# PCB_ArduinoShield_v2.net
KiCad netlist of a schematic drawn in EasyEDA
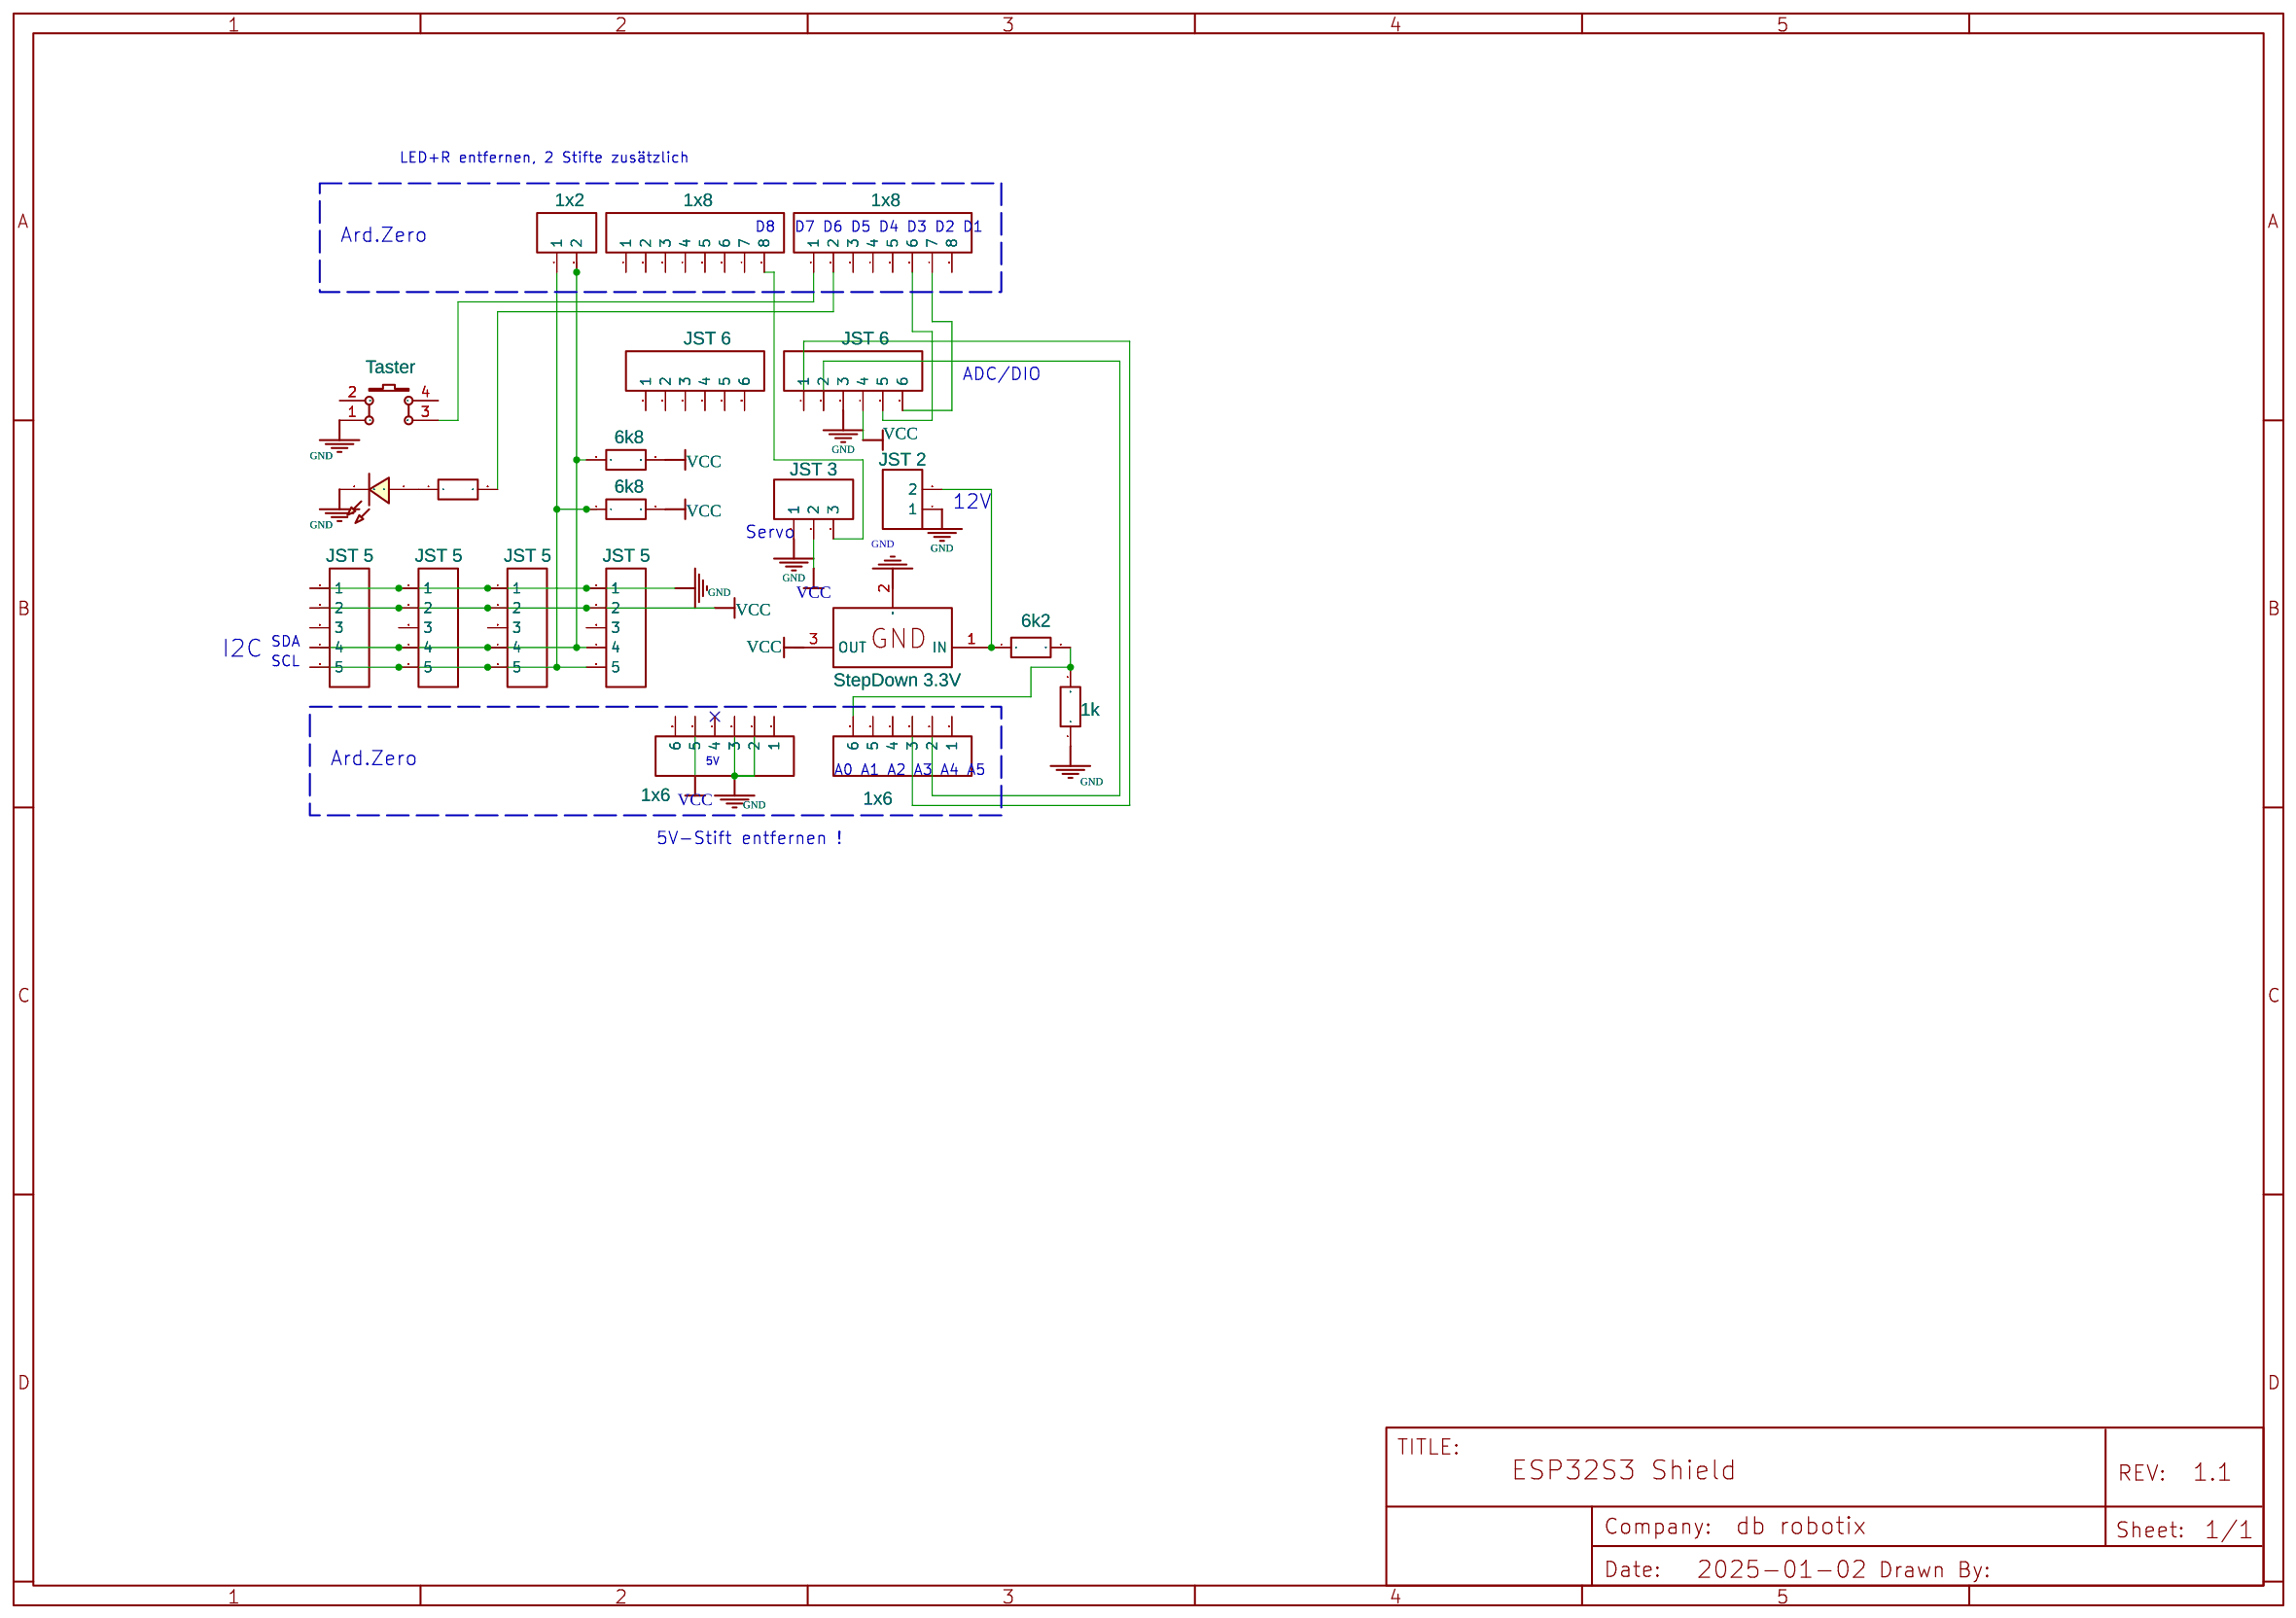
[diagram p0: schematic sheet]

(export (version "E")
  (design (tool "Eeschema 10.0.6"))
  (components
    (comp (ref "H1") (value "1x8") (libsource (lib "") (part "HDR-F-2.54_1x8")))
    (comp (ref "H2") (value "1x8") (libsource (lib "") (part "HDR-F-2.54_1x8")))
    (comp (ref "H3") (value "1x2") (libsource (lib "") (part "HDR-F-2.54_1x2")))
    (comp (ref "H4") (value "1x6") (libsource (lib "") (part "HDR-F-2.54_1x6_1")))
    (comp (ref "H5") (value "1x6") (libsource (lib "") (part "HDR-F-2.54_1x6_1")))
    (comp (ref "H6") (value "JST 6") (libsource (lib "") (part "HDR-F-2.54_1x6")))
    (comp (ref "H7") (value "JST 6") (libsource (lib "") (part "HDR-F-2.54_1x6")))
    (comp (ref "H8") (value "JST 3") (libsource (lib "") (part "HDR-F-2.54_1x3")))
    (comp (ref "H9") (value "JST 5") (libsource (lib "") (part "HDR-F-2.54_1x5")))
    (comp (ref "H10") (value "JST 5") (libsource (lib "") (part "HDR-F-2.54_1x5")))
    (comp (ref "H11") (value "JST 5") (libsource (lib "") (part "HDR-F-2.54_1x5")))
    (comp (ref "H12") (value "JST 5") (libsource (lib "") (part "HDR-F-2.54_1x5")))
    (comp (ref "H13") (value "JST 2") (libsource (lib "") (part "HDR-F-2.54_1x2_1")))
    (comp (ref "KEY1")
      (value "Taster")
      (fields (field (name "Manufacturer Part") "K2-1102DP-E4SW-04") (field (name "Manufacturer") "韩国韩荣"))
      (libsource (lib "") (part "K4-6×6_TH"))
    )
    (comp (ref "LED1")
      (value "LED-0603_R")
      (fields
        (field (name "Manufacturer Part") "19-217/R6C-AL1M2VY/3T")
        (field (name "Manufacturer") "EVERLIGHT(台湾亿光)")
      )
      (libsource (lib "") (part "LED-0603_R"))
    )
    (comp (ref "R1") (value "6k2") (libsource (lib "") (part "R_0603_EU")))
    (comp (ref "R2") (value "1k") (libsource (lib "") (part "R_0603_EU_1")))
    (comp (ref "R3") (value "1k") (libsource (lib "") (part "R_0603_EU")))
    (comp (ref "R4") (value "6k8") (libsource (lib "") (part "R_0603_EU")))
    (comp (ref "R5") (value "6k8") (libsource (lib "") (part "R_0603_EU")))
    (comp (ref "U1")
      (value "StepDown 3.3V")
      (fields
        (field (name "Manufacturer Part") "L7805CV-DG")
        (field (name "Manufacturer") "STMicroelectronics")
      )
      (libsource (lib "") (part "7805(TO-220)"))
    )
  )
  (nets
    (net (code "1") (name "GND") (class "Default")
      (node (ref "H10") (pin "1") (pinfunction "1_1") (pintype "unspecified"))
      (node (ref "H11") (pin "1") (pinfunction "1_1") (pintype "unspecified"))
      (node (ref "H12") (pin "1") (pinfunction "1_1") (pintype "unspecified"))
      (node (ref "H13") (pin "1") (pinfunction "1_1") (pintype "input"))
      (node (ref "H5") (pin "2") (pinfunction "2_2") (pintype "input"))
      (node (ref "H5") (pin "3") (pinfunction "3_3") (pintype "input"))
      (node (ref "H7") (pin "3") (pinfunction "3_3") (pintype "input"))
      (node (ref "H8") (pin "1") (pinfunction "1_1") (pintype "input"))
      (node (ref "KEY1") (pin "1") (pinfunction "1_1") (pintype "unspecified"))
      (node (ref "LED1") (pin "2") (pinfunction "2_2") (pintype "unspecified"))
      (node (ref "R2") (pin "1") (pinfunction "1_1") (pintype "unspecified"))
    )
    (net (code "2") (name "Net-(H1-Pad1)") (class "Default")
      (node (ref "H1") (pin "1") (pinfunction "1_1") (pintype "unspecified"))
      (node (ref "KEY1") (pin "3") (pinfunction "3_3") (pintype "unspecified"))
    )
    (net (code "3") (name "Net-(H1-Pad2)") (class "Default")
      (node (ref "H1") (pin "2") (pinfunction "2_2") (pintype "unspecified"))
      (node (ref "R3") (pin "2") (pinfunction "2_2") (pintype "unspecified"))
    )
    (net (code "4") (name "Net-(H1-Pad6)") (class "Default")
      (node (ref "H1") (pin "6") (pinfunction "6_6") (pintype "unspecified"))
      (node (ref "H7") (pin "5") (pinfunction "5_5") (pintype "input"))
    )
    (net (code "5") (name "Net-(H1-Pad7)") (class "Default")
      (node (ref "H1") (pin "7") (pinfunction "7_7") (pintype "unspecified"))
      (node (ref "H7") (pin "6") (pinfunction "6_6") (pintype "input"))
    )
    (net (code "6") (name "Net-(H2-Pad8)") (class "Default")
      (node (ref "H2") (pin "8") (pinfunction "8_8") (pintype "unspecified"))
      (node (ref "H8") (pin "3") (pinfunction "3_3") (pintype "input"))
    )
    (net (code "7") (name "Net-(H4-Pad2)") (class "Default")
      (node (ref "H4") (pin "2") (pinfunction "2_2") (pintype "input"))
      (node (ref "H7") (pin "2") (pinfunction "2_2") (pintype "input"))
    )
    (net (code "8") (name "Net-(H4-Pad3)") (class "Default")
      (node (ref "H4") (pin "3") (pinfunction "3_3") (pintype "input"))
      (node (ref "H7") (pin "1") (pinfunction "1_1") (pintype "input"))
    )
    (net (code "9") (name "Net-(H4-Pad6)") (class "Default")
      (node (ref "H4") (pin "6") (pinfunction "6_6") (pintype "input"))
      (node (ref "R1") (pin "2") (pinfunction "2_2") (pintype "unspecified"))
      (node (ref "R2") (pin "2") (pinfunction "2_2") (pintype "unspecified"))
    )
    (net (code "10") (name "Net-(H10-Pad4)") (class "Default")
      (node (ref "H10") (pin "4") (pinfunction "4_4") (pintype "unspecified"))
      (node (ref "H11") (pin "4") (pinfunction "4_4") (pintype "unspecified"))
      (node (ref "H12") (pin "4") (pinfunction "4_4") (pintype "unspecified"))
      (node (ref "H3") (pin "2") (pinfunction "2_2") (pintype "input"))
      (node (ref "R4") (pin "1") (pinfunction "1_1") (pintype "unspecified"))
    )
    (net (code "11") (name "Net-(H10-Pad5)") (class "Default")
      (node (ref "H10") (pin "5") (pinfunction "5_5") (pintype "unspecified"))
      (node (ref "H11") (pin "5") (pinfunction "5_5") (pintype "unspecified"))
      (node (ref "H12") (pin "5") (pinfunction "5_5") (pintype "unspecified"))
      (node (ref "H3") (pin "1") (pinfunction "1_1") (pintype "input"))
      (node (ref "R5") (pin "1") (pinfunction "1_1") (pintype "unspecified"))
    )
    (net (code "12") (name "Net-(LED1-Pad1)") (class "Default")
      (node (ref "LED1") (pin "1") (pinfunction "1_1") (pintype "unspecified"))
      (node (ref "R3") (pin "1") (pinfunction "1_1") (pintype "unspecified"))
    )
    (net (code "13") (name "Net-(U1-IN)") (class "Default")
      (node (ref "H13") (pin "2") (pinfunction "2_2") (pintype "input"))
      (node (ref "R1") (pin "1") (pinfunction "1_1") (pintype "unspecified"))
      (node (ref "U1") (pin "1") (pinfunction "IN_1") (pintype "passive"))
    )
    (net (code "14") (name "VCC") (class "Default")
      (node (ref "H10") (pin "2") (pinfunction "2_2") (pintype "unspecified"))
      (node (ref "H11") (pin "2") (pinfunction "2_2") (pintype "unspecified"))
      (node (ref "H12") (pin "2") (pinfunction "2_2") (pintype "unspecified"))
      (node (ref "H5") (pin "5") (pinfunction "5_5") (pintype "input"))
      (node (ref "H7") (pin "4") (pinfunction "4_4") (pintype "input"))
      (node (ref "H8") (pin "2") (pinfunction "2_2") (pintype "input"))
      (node (ref "R4") (pin "2") (pinfunction "2_2") (pintype "unspecified"))
      (node (ref "R5") (pin "2") (pinfunction "2_2") (pintype "unspecified"))
    )
    (net (code "15") (name "unconnected-(H1-Pad3)") (class "Default")
      (node (ref "H1") (pin "3") (pinfunction "3_3") (pintype "unspecified"))
    )
    (net (code "16") (name "unconnected-(H1-Pad4)") (class "Default")
      (node (ref "H1") (pin "4") (pinfunction "4_4") (pintype "unspecified"))
    )
    (net (code "17") (name "unconnected-(H1-Pad5)") (class "Default")
      (node (ref "H1") (pin "5") (pinfunction "5_5") (pintype "unspecified"))
    )
    (net (code "18") (name "unconnected-(H1-Pad8)") (class "Default")
      (node (ref "H1") (pin "8") (pinfunction "8_8") (pintype "unspecified"))
    )
    (net (code "19") (name "unconnected-(H2-Pad1)") (class "Default")
      (node (ref "H2") (pin "1") (pinfunction "1_1") (pintype "unspecified"))
    )
    (net (code "20") (name "unconnected-(H2-Pad2)") (class "Default")
      (node (ref "H2") (pin "2") (pinfunction "2_2") (pintype "unspecified"))
    )
    (net (code "21") (name "unconnected-(H2-Pad3)") (class "Default")
      (node (ref "H2") (pin "3") (pinfunction "3_3") (pintype "unspecified"))
    )
    (net (code "22") (name "unconnected-(H2-Pad4)") (class "Default")
      (node (ref "H2") (pin "4") (pinfunction "4_4") (pintype "unspecified"))
    )
    (net (code "23") (name "unconnected-(H2-Pad5)") (class "Default")
      (node (ref "H2") (pin "5") (pinfunction "5_5") (pintype "unspecified"))
    )
    (net (code "24") (name "unconnected-(H2-Pad6)") (class "Default")
      (node (ref "H2") (pin "6") (pinfunction "6_6") (pintype "unspecified"))
    )
    (net (code "25") (name "unconnected-(H2-Pad7)") (class "Default")
      (node (ref "H2") (pin "7") (pinfunction "7_7") (pintype "unspecified"))
    )
    (net (code "26") (name "unconnected-(H4-Pad1)") (class "Default")
      (node (ref "H4") (pin "1") (pinfunction "1_1") (pintype "input"))
    )
    (net (code "27") (name "unconnected-(H4-Pad4)") (class "Default")
      (node (ref "H4") (pin "4") (pinfunction "4_4") (pintype "input"))
    )
    (net (code "28") (name "unconnected-(H4-Pad5)") (class "Default")
      (node (ref "H4") (pin "5") (pinfunction "5_5") (pintype "input"))
    )
    (net (code "29") (name "unconnected-(H5-Pad1)") (class "Default")
      (node (ref "H5") (pin "1") (pinfunction "1_1") (pintype "input"))
    )
    (net (code "30") (name "unconnected-(H5-Pad4)") (class "Default")
      (node (ref "H5") (pin "4") (pinfunction "4_4") (pintype "input+no_connect"))
    )
    (net (code "31") (name "unconnected-(H5-Pad6)") (class "Default")
      (node (ref "H5") (pin "6") (pinfunction "6_6") (pintype "input"))
    )
    (net (code "32") (name "unconnected-(H6-Pad1)") (class "Default")
      (node (ref "H6") (pin "1") (pinfunction "1_1") (pintype "input"))
    )
    (net (code "33") (name "unconnected-(H6-Pad2)") (class "Default")
      (node (ref "H6") (pin "2") (pinfunction "2_2") (pintype "input"))
    )
    (net (code "34") (name "unconnected-(H6-Pad3)") (class "Default")
      (node (ref "H6") (pin "3") (pinfunction "3_3") (pintype "input"))
    )
    (net (code "35") (name "unconnected-(H6-Pad4)") (class "Default")
      (node (ref "H6") (pin "4") (pinfunction "4_4") (pintype "input"))
    )
    (net (code "36") (name "unconnected-(H6-Pad5)") (class "Default")
      (node (ref "H6") (pin "5") (pinfunction "5_5") (pintype "input"))
    )
    (net (code "37") (name "unconnected-(H6-Pad6)") (class "Default")
      (node (ref "H6") (pin "6") (pinfunction "6_6") (pintype "input"))
    )
    (net (code "38") (name "unconnected-(H9-Pad1)") (class "Default")
      (node (ref "H9") (pin "1") (pinfunction "1_1") (pintype "unspecified"))
    )
    (net (code "39") (name "unconnected-(H9-Pad2)") (class "Default")
      (node (ref "H9") (pin "2") (pinfunction "2_2") (pintype "unspecified"))
    )
    (net (code "40") (name "unconnected-(H9-Pad3)") (class "Default")
      (node (ref "H9") (pin "3") (pinfunction "3_3") (pintype "unspecified"))
    )
    (net (code "41") (name "unconnected-(H9-Pad4)") (class "Default")
      (node (ref "H9") (pin "4") (pinfunction "4_4") (pintype "unspecified"))
    )
    (net (code "42") (name "unconnected-(H9-Pad5)") (class "Default")
      (node (ref "H9") (pin "5") (pinfunction "5_5") (pintype "unspecified"))
    )
    (net (code "43") (name "unconnected-(H10-Pad3)") (class "Default")
      (node (ref "H10") (pin "3") (pinfunction "3_3") (pintype "unspecified"))
    )
    (net (code "44") (name "unconnected-(H11-Pad3)") (class "Default")
      (node (ref "H11") (pin "3") (pinfunction "3_3") (pintype "unspecified"))
    )
    (net (code "45") (name "unconnected-(H12-Pad3)") (class "Default")
      (node (ref "H12") (pin "3") (pinfunction "3_3") (pintype "unspecified"))
    )
    (net (code "46") (name "unconnected-(KEY1-Pad2)") (class "Default")
      (node (ref "KEY1") (pin "2") (pinfunction "2_2") (pintype "unspecified"))
    )
    (net (code "47") (name "unconnected-(KEY1-Pad4)") (class "Default")
      (node (ref "KEY1") (pin "4") (pinfunction "4_4") (pintype "unspecified"))
    )
    (net (code "48") (name "unconnected-(U1-GND-Pad2)") (class "Default")
      (node (ref "U1") (pin "2") (pinfunction "GND_2") (pintype "passive"))
    )
    (net (code "49") (name "unconnected-(U1-OUT-Pad3)") (class "Default")
      (node (ref "U1") (pin "3") (pinfunction "OUT_3") (pintype "passive"))
    )
  )
)
